# input2.net
KiCad netlist of a schematic drawn in Altium Designer
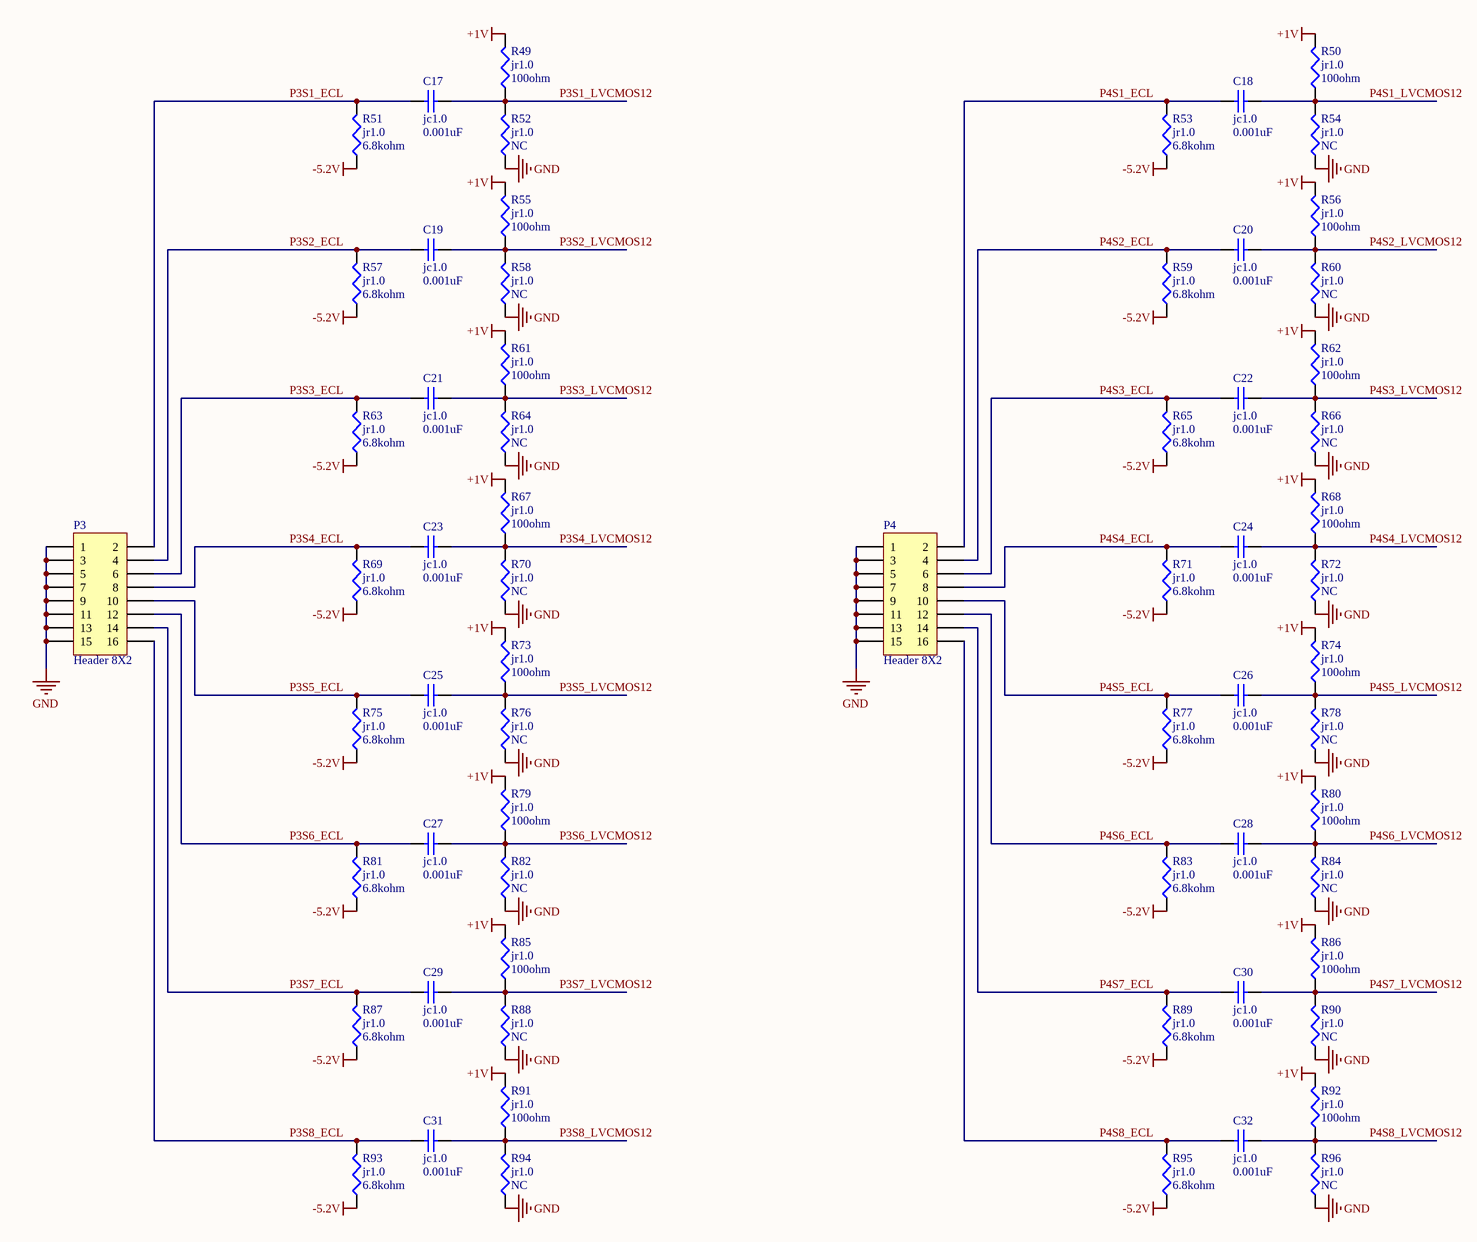
[diagram p0: input2.SchDoc]

(export (version "E")
  (design (tool "Eeschema 10.0.6"))
  (components
    (comp (ref "C17")
      (value "jc1.0")
      (footprint "0402")
      (description "Capacitor")
      (fields (field (name "ALTIUM_VALUE") "0.001uF") (field (name "PUBLISHER") "Altium Limited"))
      (libsource (lib "LIB01DXP2006SchLib") (part "Cap"))
    )
    (comp (ref "C18")
      (value "jc1.0")
      (footprint "0402")
      (description "Capacitor")
      (fields (field (name "ALTIUM_VALUE") "0.001uF") (field (name "PUBLISHER") "Altium Limited"))
      (libsource (lib "LIB01DXP2006SchLib") (part "Cap"))
    )
    (comp (ref "C19")
      (value "jc1.0")
      (footprint "0402")
      (description "Capacitor")
      (fields (field (name "ALTIUM_VALUE") "0.001uF") (field (name "PUBLISHER") "Altium Limited"))
      (libsource (lib "LIB01DXP2006SchLib") (part "Cap"))
    )
    (comp (ref "C20")
      (value "jc1.0")
      (footprint "0402")
      (description "Capacitor")
      (fields (field (name "ALTIUM_VALUE") "0.001uF") (field (name "PUBLISHER") "Altium Limited"))
      (libsource (lib "LIB01DXP2006SchLib") (part "Cap"))
    )
    (comp (ref "C21")
      (value "jc1.0")
      (footprint "0402")
      (description "Capacitor")
      (fields (field (name "ALTIUM_VALUE") "0.001uF") (field (name "PUBLISHER") "Altium Limited"))
      (libsource (lib "LIB01DXP2006SchLib") (part "Cap"))
    )
    (comp (ref "C22")
      (value "jc1.0")
      (footprint "0402")
      (description "Capacitor")
      (fields (field (name "ALTIUM_VALUE") "0.001uF") (field (name "PUBLISHER") "Altium Limited"))
      (libsource (lib "LIB01DXP2006SchLib") (part "Cap"))
    )
    (comp (ref "C23")
      (value "jc1.0")
      (footprint "0402")
      (description "Capacitor")
      (fields (field (name "ALTIUM_VALUE") "0.001uF") (field (name "PUBLISHER") "Altium Limited"))
      (libsource (lib "LIB01DXP2006SchLib") (part "Cap"))
    )
    (comp (ref "C24")
      (value "jc1.0")
      (footprint "0402")
      (description "Capacitor")
      (fields (field (name "ALTIUM_VALUE") "0.001uF") (field (name "PUBLISHER") "Altium Limited"))
      (libsource (lib "LIB01DXP2006SchLib") (part "Cap"))
    )
    (comp (ref "C25")
      (value "jc1.0")
      (footprint "0402")
      (description "Capacitor")
      (fields (field (name "ALTIUM_VALUE") "0.001uF") (field (name "PUBLISHER") "Altium Limited"))
      (libsource (lib "LIB01DXP2006SchLib") (part "Cap"))
    )
    (comp (ref "C26")
      (value "jc1.0")
      (footprint "0402")
      (description "Capacitor")
      (fields (field (name "ALTIUM_VALUE") "0.001uF") (field (name "PUBLISHER") "Altium Limited"))
      (libsource (lib "LIB01DXP2006SchLib") (part "Cap"))
    )
    (comp (ref "C27")
      (value "jc1.0")
      (footprint "0402")
      (description "Capacitor")
      (fields (field (name "ALTIUM_VALUE") "0.001uF") (field (name "PUBLISHER") "Altium Limited"))
      (libsource (lib "LIB01DXP2006SchLib") (part "Cap"))
    )
    (comp (ref "C28")
      (value "jc1.0")
      (footprint "0402")
      (description "Capacitor")
      (fields (field (name "ALTIUM_VALUE") "0.001uF") (field (name "PUBLISHER") "Altium Limited"))
      (libsource (lib "LIB01DXP2006SchLib") (part "Cap"))
    )
    (comp (ref "C29")
      (value "jc1.0")
      (footprint "0402")
      (description "Capacitor")
      (fields (field (name "ALTIUM_VALUE") "0.001uF") (field (name "PUBLISHER") "Altium Limited"))
      (libsource (lib "LIB01DXP2006SchLib") (part "Cap"))
    )
    (comp (ref "C30")
      (value "jc1.0")
      (footprint "0402")
      (description "Capacitor")
      (fields (field (name "ALTIUM_VALUE") "0.001uF") (field (name "PUBLISHER") "Altium Limited"))
      (libsource (lib "LIB01DXP2006SchLib") (part "Cap"))
    )
    (comp (ref "C31")
      (value "jc1.0")
      (footprint "0402")
      (description "Capacitor")
      (fields (field (name "ALTIUM_VALUE") "0.001uF") (field (name "PUBLISHER") "Altium Limited"))
      (libsource (lib "LIB01DXP2006SchLib") (part "Cap"))
    )
    (comp (ref "C32")
      (value "jc1.0")
      (footprint "0402")
      (description "Capacitor")
      (fields (field (name "ALTIUM_VALUE") "0.001uF") (field (name "PUBLISHER") "Altium Limited"))
      (libsource (lib "LIB01DXP2006SchLib") (part "Cap"))
    )
    (comp (ref "P3")
      (value "Header 8X2")
      (footprint "HDR2X8")
      (description "Header, 8-Pin, Dual row")
      (fields (field (name "PUBLISHER") "Altium Limited"))
      (libsource (lib "Miscellaneous Connectors") (part "Header 8X2"))
    )
    (comp (ref "P4")
      (value "Header 8X2")
      (footprint "HDR2X8")
      (description "Header, 8-Pin, Dual row")
      (fields (field (name "PUBLISHER") "Altium Limited"))
      (libsource (lib "Miscellaneous Connectors") (part "Header 8X2"))
    )
    (comp (ref "R49")
      (value "jr1.0")
      (footprint "0402")
      (description "Resistor")
      (fields (field (name "ALTIUM_VALUE") "100ohm") (field (name "PUBLISHER") "Altium Limited"))
      (libsource (lib "LIB01DXP2006SchLib") (part "Res"))
    )
    (comp (ref "R50")
      (value "jr1.0")
      (footprint "0402")
      (description "Resistor")
      (fields (field (name "ALTIUM_VALUE") "100ohm") (field (name "PUBLISHER") "Altium Limited"))
      (libsource (lib "LIB01DXP2006SchLib") (part "Res"))
    )
    (comp (ref "R51")
      (value "jr1.0")
      (footprint "0402")
      (description "Resistor")
      (fields (field (name "ALTIUM_VALUE") "6.8kohm") (field (name "PUBLISHER") "Altium Limited"))
      (libsource (lib "LIB01DXP2006SchLib") (part "Res"))
    )
    (comp (ref "R52")
      (value "jr1.0")
      (footprint "0402")
      (description "Resistor")
      (fields (field (name "ALTIUM_VALUE") "NC") (field (name "PUBLISHER") "Altium Limited"))
      (libsource (lib "LIB01DXP2006SchLib") (part "Res"))
    )
    (comp (ref "R53")
      (value "jr1.0")
      (footprint "0402")
      (description "Resistor")
      (fields (field (name "ALTIUM_VALUE") "6.8kohm") (field (name "PUBLISHER") "Altium Limited"))
      (libsource (lib "LIB01DXP2006SchLib") (part "Res"))
    )
    (comp (ref "R54")
      (value "jr1.0")
      (footprint "0402")
      (description "Resistor")
      (fields (field (name "ALTIUM_VALUE") "NC") (field (name "PUBLISHER") "Altium Limited"))
      (libsource (lib "LIB01DXP2006SchLib") (part "Res"))
    )
    (comp (ref "R55")
      (value "jr1.0")
      (footprint "0402")
      (description "Resistor")
      (fields (field (name "ALTIUM_VALUE") "100ohm") (field (name "PUBLISHER") "Altium Limited"))
      (libsource (lib "LIB01DXP2006SchLib") (part "Res"))
    )
    (comp (ref "R56")
      (value "jr1.0")
      (footprint "0402")
      (description "Resistor")
      (fields (field (name "ALTIUM_VALUE") "100ohm") (field (name "PUBLISHER") "Altium Limited"))
      (libsource (lib "LIB01DXP2006SchLib") (part "Res"))
    )
    (comp (ref "R57")
      (value "jr1.0")
      (footprint "0402")
      (description "Resistor")
      (fields (field (name "ALTIUM_VALUE") "6.8kohm") (field (name "PUBLISHER") "Altium Limited"))
      (libsource (lib "LIB01DXP2006SchLib") (part "Res"))
    )
    (comp (ref "R58")
      (value "jr1.0")
      (footprint "0402")
      (description "Resistor")
      (fields (field (name "ALTIUM_VALUE") "NC") (field (name "PUBLISHER") "Altium Limited"))
      (libsource (lib "LIB01DXP2006SchLib") (part "Res"))
    )
    (comp (ref "R59")
      (value "jr1.0")
      (footprint "0402")
      (description "Resistor")
      (fields (field (name "ALTIUM_VALUE") "6.8kohm") (field (name "PUBLISHER") "Altium Limited"))
      (libsource (lib "LIB01DXP2006SchLib") (part "Res"))
    )
    (comp (ref "R60")
      (value "jr1.0")
      (footprint "0402")
      (description "Resistor")
      (fields (field (name "ALTIUM_VALUE") "NC") (field (name "PUBLISHER") "Altium Limited"))
      (libsource (lib "LIB01DXP2006SchLib") (part "Res"))
    )
    (comp (ref "R61")
      (value "jr1.0")
      (footprint "0402")
      (description "Resistor")
      (fields (field (name "ALTIUM_VALUE") "100ohm") (field (name "PUBLISHER") "Altium Limited"))
      (libsource (lib "LIB01DXP2006SchLib") (part "Res"))
    )
    (comp (ref "R62")
      (value "jr1.0")
      (footprint "0402")
      (description "Resistor")
      (fields (field (name "ALTIUM_VALUE") "100ohm") (field (name "PUBLISHER") "Altium Limited"))
      (libsource (lib "LIB01DXP2006SchLib") (part "Res"))
    )
    (comp (ref "R63")
      (value "jr1.0")
      (footprint "0402")
      (description "Resistor")
      (fields (field (name "ALTIUM_VALUE") "6.8kohm") (field (name "PUBLISHER") "Altium Limited"))
      (libsource (lib "LIB01DXP2006SchLib") (part "Res"))
    )
    (comp (ref "R64")
      (value "jr1.0")
      (footprint "0402")
      (description "Resistor")
      (fields (field (name "ALTIUM_VALUE") "NC") (field (name "PUBLISHER") "Altium Limited"))
      (libsource (lib "LIB01DXP2006SchLib") (part "Res"))
    )
    (comp (ref "R65")
      (value "jr1.0")
      (footprint "0402")
      (description "Resistor")
      (fields (field (name "ALTIUM_VALUE") "6.8kohm") (field (name "PUBLISHER") "Altium Limited"))
      (libsource (lib "LIB01DXP2006SchLib") (part "Res"))
    )
    (comp (ref "R66")
      (value "jr1.0")
      (footprint "0402")
      (description "Resistor")
      (fields (field (name "ALTIUM_VALUE") "NC") (field (name "PUBLISHER") "Altium Limited"))
      (libsource (lib "LIB01DXP2006SchLib") (part "Res"))
    )
    (comp (ref "R67")
      (value "jr1.0")
      (footprint "0402")
      (description "Resistor")
      (fields (field (name "ALTIUM_VALUE") "100ohm") (field (name "PUBLISHER") "Altium Limited"))
      (libsource (lib "LIB01DXP2006SchLib") (part "Res"))
    )
    (comp (ref "R68")
      (value "jr1.0")
      (footprint "0402")
      (description "Resistor")
      (fields (field (name "ALTIUM_VALUE") "100ohm") (field (name "PUBLISHER") "Altium Limited"))
      (libsource (lib "LIB01DXP2006SchLib") (part "Res"))
    )
    (comp (ref "R69")
      (value "jr1.0")
      (footprint "0402")
      (description "Resistor")
      (fields (field (name "ALTIUM_VALUE") "6.8kohm") (field (name "PUBLISHER") "Altium Limited"))
      (libsource (lib "LIB01DXP2006SchLib") (part "Res"))
    )
    (comp (ref "R70")
      (value "jr1.0")
      (footprint "0402")
      (description "Resistor")
      (fields (field (name "ALTIUM_VALUE") "NC") (field (name "PUBLISHER") "Altium Limited"))
      (libsource (lib "LIB01DXP2006SchLib") (part "Res"))
    )
    (comp (ref "R71")
      (value "jr1.0")
      (footprint "0402")
      (description "Resistor")
      (fields (field (name "ALTIUM_VALUE") "6.8kohm") (field (name "PUBLISHER") "Altium Limited"))
      (libsource (lib "LIB01DXP2006SchLib") (part "Res"))
    )
    (comp (ref "R72")
      (value "jr1.0")
      (footprint "0402")
      (description "Resistor")
      (fields (field (name "ALTIUM_VALUE") "NC") (field (name "PUBLISHER") "Altium Limited"))
      (libsource (lib "LIB01DXP2006SchLib") (part "Res"))
    )
    (comp (ref "R73")
      (value "jr1.0")
      (footprint "0402")
      (description "Resistor")
      (fields (field (name "ALTIUM_VALUE") "100ohm") (field (name "PUBLISHER") "Altium Limited"))
      (libsource (lib "LIB01DXP2006SchLib") (part "Res"))
    )
    (comp (ref "R74")
      (value "jr1.0")
      (footprint "0402")
      (description "Resistor")
      (fields (field (name "ALTIUM_VALUE") "100ohm") (field (name "PUBLISHER") "Altium Limited"))
      (libsource (lib "LIB01DXP2006SchLib") (part "Res"))
    )
    (comp (ref "R75")
      (value "jr1.0")
      (footprint "0402")
      (description "Resistor")
      (fields (field (name "ALTIUM_VALUE") "6.8kohm") (field (name "PUBLISHER") "Altium Limited"))
      (libsource (lib "LIB01DXP2006SchLib") (part "Res"))
    )
    (comp (ref "R76")
      (value "jr1.0")
      (footprint "0402")
      (description "Resistor")
      (fields (field (name "ALTIUM_VALUE") "NC") (field (name "PUBLISHER") "Altium Limited"))
      (libsource (lib "LIB01DXP2006SchLib") (part "Res"))
    )
    (comp (ref "R77")
      (value "jr1.0")
      (footprint "0402")
      (description "Resistor")
      (fields (field (name "ALTIUM_VALUE") "6.8kohm") (field (name "PUBLISHER") "Altium Limited"))
      (libsource (lib "LIB01DXP2006SchLib") (part "Res"))
    )
    (comp (ref "R78")
      (value "jr1.0")
      (footprint "0402")
      (description "Resistor")
      (fields (field (name "ALTIUM_VALUE") "NC") (field (name "PUBLISHER") "Altium Limited"))
      (libsource (lib "LIB01DXP2006SchLib") (part "Res"))
    )
    (comp (ref "R79")
      (value "jr1.0")
      (footprint "0402")
      (description "Resistor")
      (fields (field (name "ALTIUM_VALUE") "100ohm") (field (name "PUBLISHER") "Altium Limited"))
      (libsource (lib "LIB01DXP2006SchLib") (part "Res"))
    )
    (comp (ref "R80")
      (value "jr1.0")
      (footprint "0402")
      (description "Resistor")
      (fields (field (name "ALTIUM_VALUE") "100ohm") (field (name "PUBLISHER") "Altium Limited"))
      (libsource (lib "LIB01DXP2006SchLib") (part "Res"))
    )
    (comp (ref "R81")
      (value "jr1.0")
      (footprint "0402")
      (description "Resistor")
      (fields (field (name "ALTIUM_VALUE") "6.8kohm") (field (name "PUBLISHER") "Altium Limited"))
      (libsource (lib "LIB01DXP2006SchLib") (part "Res"))
    )
    (comp (ref "R82")
      (value "jr1.0")
      (footprint "0402")
      (description "Resistor")
      (fields (field (name "ALTIUM_VALUE") "NC") (field (name "PUBLISHER") "Altium Limited"))
      (libsource (lib "LIB01DXP2006SchLib") (part "Res"))
    )
    (comp (ref "R83")
      (value "jr1.0")
      (footprint "0402")
      (description "Resistor")
      (fields (field (name "ALTIUM_VALUE") "6.8kohm") (field (name "PUBLISHER") "Altium Limited"))
      (libsource (lib "LIB01DXP2006SchLib") (part "Res"))
    )
    (comp (ref "R84")
      (value "jr1.0")
      (footprint "0402")
      (description "Resistor")
      (fields (field (name "ALTIUM_VALUE") "NC") (field (name "PUBLISHER") "Altium Limited"))
      (libsource (lib "LIB01DXP2006SchLib") (part "Res"))
    )
    (comp (ref "R85")
      (value "jr1.0")
      (footprint "0402")
      (description "Resistor")
      (fields (field (name "ALTIUM_VALUE") "100ohm") (field (name "PUBLISHER") "Altium Limited"))
      (libsource (lib "LIB01DXP2006SchLib") (part "Res"))
    )
    (comp (ref "R86")
      (value "jr1.0")
      (footprint "0402")
      (description "Resistor")
      (fields (field (name "ALTIUM_VALUE") "100ohm") (field (name "PUBLISHER") "Altium Limited"))
      (libsource (lib "LIB01DXP2006SchLib") (part "Res"))
    )
    (comp (ref "R87")
      (value "jr1.0")
      (footprint "0402")
      (description "Resistor")
      (fields (field (name "ALTIUM_VALUE") "6.8kohm") (field (name "PUBLISHER") "Altium Limited"))
      (libsource (lib "LIB01DXP2006SchLib") (part "Res"))
    )
    (comp (ref "R88")
      (value "jr1.0")
      (footprint "0402")
      (description "Resistor")
      (fields (field (name "ALTIUM_VALUE") "NC") (field (name "PUBLISHER") "Altium Limited"))
      (libsource (lib "LIB01DXP2006SchLib") (part "Res"))
    )
    (comp (ref "R89")
      (value "jr1.0")
      (footprint "0402")
      (description "Resistor")
      (fields (field (name "ALTIUM_VALUE") "6.8kohm") (field (name "PUBLISHER") "Altium Limited"))
      (libsource (lib "LIB01DXP2006SchLib") (part "Res"))
    )
    (comp (ref "R90")
      (value "jr1.0")
      (footprint "0402")
      (description "Resistor")
      (fields (field (name "ALTIUM_VALUE") "NC") (field (name "PUBLISHER") "Altium Limited"))
      (libsource (lib "LIB01DXP2006SchLib") (part "Res"))
    )
    (comp (ref "R91")
      (value "jr1.0")
      (footprint "0402")
      (description "Resistor")
      (fields (field (name "ALTIUM_VALUE") "100ohm") (field (name "PUBLISHER") "Altium Limited"))
      (libsource (lib "LIB01DXP2006SchLib") (part "Res"))
    )
    (comp (ref "R92")
      (value "jr1.0")
      (footprint "0402")
      (description "Resistor")
      (fields (field (name "ALTIUM_VALUE") "100ohm") (field (name "PUBLISHER") "Altium Limited"))
      (libsource (lib "LIB01DXP2006SchLib") (part "Res"))
    )
    (comp (ref "R93")
      (value "jr1.0")
      (footprint "0402")
      (description "Resistor")
      (fields (field (name "ALTIUM_VALUE") "6.8kohm") (field (name "PUBLISHER") "Altium Limited"))
      (libsource (lib "LIB01DXP2006SchLib") (part "Res"))
    )
    (comp (ref "R94")
      (value "jr1.0")
      (footprint "0402")
      (description "Resistor")
      (fields (field (name "ALTIUM_VALUE") "NC") (field (name "PUBLISHER") "Altium Limited"))
      (libsource (lib "LIB01DXP2006SchLib") (part "Res"))
    )
    (comp (ref "R95")
      (value "jr1.0")
      (footprint "0402")
      (description "Resistor")
      (fields (field (name "ALTIUM_VALUE") "6.8kohm") (field (name "PUBLISHER") "Altium Limited"))
      (libsource (lib "LIB01DXP2006SchLib") (part "Res"))
    )
    (comp (ref "R96")
      (value "jr1.0")
      (footprint "0402")
      (description "Resistor")
      (fields (field (name "ALTIUM_VALUE") "NC") (field (name "PUBLISHER") "Altium Limited"))
      (libsource (lib "LIB01DXP2006SchLib") (part "Res"))
    )
  )
  (nets
    (net (code "1") (name "+1V") (class "Default")
      (node (ref "R49") (pin "2") (pinfunction "2_2") (pintype "passive"))
      (node (ref "R50") (pin "2") (pinfunction "2_2") (pintype "passive"))
      (node (ref "R55") (pin "2") (pinfunction "2_2") (pintype "passive"))
      (node (ref "R56") (pin "2") (pinfunction "2_2") (pintype "passive"))
      (node (ref "R61") (pin "2") (pinfunction "2_2") (pintype "passive"))
      (node (ref "R62") (pin "2") (pinfunction "2_2") (pintype "passive"))
      (node (ref "R67") (pin "2") (pinfunction "2_2") (pintype "passive"))
      (node (ref "R68") (pin "2") (pinfunction "2_2") (pintype "passive"))
      (node (ref "R73") (pin "2") (pinfunction "2_2") (pintype "passive"))
      (node (ref "R74") (pin "2") (pinfunction "2_2") (pintype "passive"))
      (node (ref "R79") (pin "2") (pinfunction "2_2") (pintype "passive"))
      (node (ref "R80") (pin "2") (pinfunction "2_2") (pintype "passive"))
      (node (ref "R85") (pin "2") (pinfunction "2_2") (pintype "passive"))
      (node (ref "R86") (pin "2") (pinfunction "2_2") (pintype "passive"))
      (node (ref "R91") (pin "2") (pinfunction "2_2") (pintype "passive"))
      (node (ref "R92") (pin "2") (pinfunction "2_2") (pintype "passive"))
    )
    (net (code "2") (name "-5.2V") (class "Default")
      (node (ref "R51") (pin "1") (pinfunction "1_1") (pintype "passive"))
      (node (ref "R53") (pin "1") (pinfunction "1_1") (pintype "passive"))
      (node (ref "R57") (pin "1") (pinfunction "1_1") (pintype "passive"))
      (node (ref "R59") (pin "1") (pinfunction "1_1") (pintype "passive"))
      (node (ref "R63") (pin "1") (pinfunction "1_1") (pintype "passive"))
      (node (ref "R65") (pin "1") (pinfunction "1_1") (pintype "passive"))
      (node (ref "R69") (pin "1") (pinfunction "1_1") (pintype "passive"))
      (node (ref "R71") (pin "1") (pinfunction "1_1") (pintype "passive"))
      (node (ref "R75") (pin "1") (pinfunction "1_1") (pintype "passive"))
      (node (ref "R77") (pin "1") (pinfunction "1_1") (pintype "passive"))
      (node (ref "R81") (pin "1") (pinfunction "1_1") (pintype "passive"))
      (node (ref "R83") (pin "1") (pinfunction "1_1") (pintype "passive"))
      (node (ref "R87") (pin "1") (pinfunction "1_1") (pintype "passive"))
      (node (ref "R89") (pin "1") (pinfunction "1_1") (pintype "passive"))
      (node (ref "R93") (pin "1") (pinfunction "1_1") (pintype "passive"))
      (node (ref "R95") (pin "1") (pinfunction "1_1") (pintype "passive"))
    )
    (net (code "3") (name "/P3S1_ECL") (class "Default")
      (node (ref "C17") (pin "1") (pinfunction "1_1") (pintype "passive"))
      (node (ref "P3") (pin "2") (pinfunction "2_2") (pintype "passive"))
      (node (ref "R51") (pin "2") (pinfunction "2_2") (pintype "passive"))
    )
    (net (code "4") (name "/P3S1_LVCMOS12") (class "Default")
      (node (ref "C17") (pin "2") (pinfunction "2_2") (pintype "passive"))
      (node (ref "R49") (pin "1") (pinfunction "1_1") (pintype "passive"))
      (node (ref "R52") (pin "2") (pinfunction "2_2") (pintype "passive"))
    )
    (net (code "5") (name "/P3S2_ECL") (class "Default")
      (node (ref "C19") (pin "1") (pinfunction "1_1") (pintype "passive"))
      (node (ref "P3") (pin "4") (pinfunction "4_4") (pintype "passive"))
      (node (ref "R57") (pin "2") (pinfunction "2_2") (pintype "passive"))
    )
    (net (code "6") (name "/P3S2_LVCMOS12") (class "Default")
      (node (ref "C19") (pin "2") (pinfunction "2_2") (pintype "passive"))
      (node (ref "R55") (pin "1") (pinfunction "1_1") (pintype "passive"))
      (node (ref "R58") (pin "2") (pinfunction "2_2") (pintype "passive"))
    )
    (net (code "7") (name "/P3S3_ECL") (class "Default")
      (node (ref "C21") (pin "1") (pinfunction "1_1") (pintype "passive"))
      (node (ref "P3") (pin "6") (pinfunction "6_6") (pintype "passive"))
      (node (ref "R63") (pin "2") (pinfunction "2_2") (pintype "passive"))
    )
    (net (code "8") (name "/P3S3_LVCMOS12") (class "Default")
      (node (ref "C21") (pin "2") (pinfunction "2_2") (pintype "passive"))
      (node (ref "R61") (pin "1") (pinfunction "1_1") (pintype "passive"))
      (node (ref "R64") (pin "2") (pinfunction "2_2") (pintype "passive"))
    )
    (net (code "9") (name "/P3S4_ECL") (class "Default")
      (node (ref "C23") (pin "1") (pinfunction "1_1") (pintype "passive"))
      (node (ref "P3") (pin "8") (pinfunction "8_8") (pintype "passive"))
      (node (ref "R69") (pin "2") (pinfunction "2_2") (pintype "passive"))
    )
    (net (code "10") (name "/P3S4_LVCMOS12") (class "Default")
      (node (ref "C23") (pin "2") (pinfunction "2_2") (pintype "passive"))
      (node (ref "R67") (pin "1") (pinfunction "1_1") (pintype "passive"))
      (node (ref "R70") (pin "2") (pinfunction "2_2") (pintype "passive"))
    )
    (net (code "11") (name "/P3S5_ECL") (class "Default")
      (node (ref "C25") (pin "1") (pinfunction "1_1") (pintype "passive"))
      (node (ref "P3") (pin "10") (pinfunction "10_10") (pintype "passive"))
      (node (ref "R75") (pin "2") (pinfunction "2_2") (pintype "passive"))
    )
    (net (code "12") (name "/P3S5_LVCMOS12") (class "Default")
      (node (ref "C25") (pin "2") (pinfunction "2_2") (pintype "passive"))
      (node (ref "R73") (pin "1") (pinfunction "1_1") (pintype "passive"))
      (node (ref "R76") (pin "2") (pinfunction "2_2") (pintype "passive"))
    )
    (net (code "13") (name "/P3S6_ECL") (class "Default")
      (node (ref "C27") (pin "1") (pinfunction "1_1") (pintype "passive"))
      (node (ref "P3") (pin "12") (pinfunction "12_12") (pintype "passive"))
      (node (ref "R81") (pin "2") (pinfunction "2_2") (pintype "passive"))
    )
    (net (code "14") (name "/P3S6_LVCMOS12") (class "Default")
      (node (ref "C27") (pin "2") (pinfunction "2_2") (pintype "passive"))
      (node (ref "R79") (pin "1") (pinfunction "1_1") (pintype "passive"))
      (node (ref "R82") (pin "2") (pinfunction "2_2") (pintype "passive"))
    )
    (net (code "15") (name "/P3S7_ECL") (class "Default")
      (node (ref "C29") (pin "1") (pinfunction "1_1") (pintype "passive"))
      (node (ref "P3") (pin "14") (pinfunction "14_14") (pintype "passive"))
      (node (ref "R87") (pin "2") (pinfunction "2_2") (pintype "passive"))
    )
    (net (code "16") (name "/P3S7_LVCMOS12") (class "Default")
      (node (ref "C29") (pin "2") (pinfunction "2_2") (pintype "passive"))
      (node (ref "R85") (pin "1") (pinfunction "1_1") (pintype "passive"))
      (node (ref "R88") (pin "2") (pinfunction "2_2") (pintype "passive"))
    )
    (net (code "17") (name "/P3S8_ECL") (class "Default")
      (node (ref "C31") (pin "1") (pinfunction "1_1") (pintype "passive"))
      (node (ref "P3") (pin "16") (pinfunction "16_16") (pintype "passive"))
      (node (ref "R93") (pin "2") (pinfunction "2_2") (pintype "passive"))
    )
    (net (code "18") (name "/P3S8_LVCMOS12") (class "Default")
      (node (ref "C31") (pin "2") (pinfunction "2_2") (pintype "passive"))
      (node (ref "R91") (pin "1") (pinfunction "1_1") (pintype "passive"))
      (node (ref "R94") (pin "2") (pinfunction "2_2") (pintype "passive"))
    )
    (net (code "19") (name "/P4S1_ECL") (class "Default")
      (node (ref "C18") (pin "1") (pinfunction "1_1") (pintype "passive"))
      (node (ref "P4") (pin "2") (pinfunction "2_2") (pintype "passive"))
      (node (ref "R53") (pin "2") (pinfunction "2_2") (pintype "passive"))
    )
    (net (code "20") (name "/P4S1_LVCMOS12") (class "Default")
      (node (ref "C18") (pin "2") (pinfunction "2_2") (pintype "passive"))
      (node (ref "R50") (pin "1") (pinfunction "1_1") (pintype "passive"))
      (node (ref "R54") (pin "2") (pinfunction "2_2") (pintype "passive"))
    )
    (net (code "21") (name "/P4S2_ECL") (class "Default")
      (node (ref "C20") (pin "1") (pinfunction "1_1") (pintype "passive"))
      (node (ref "P4") (pin "4") (pinfunction "4_4") (pintype "passive"))
      (node (ref "R59") (pin "2") (pinfunction "2_2") (pintype "passive"))
    )
    (net (code "22") (name "/P4S2_LVCMOS12") (class "Default")
      (node (ref "C20") (pin "2") (pinfunction "2_2") (pintype "passive"))
      (node (ref "R56") (pin "1") (pinfunction "1_1") (pintype "passive"))
      (node (ref "R60") (pin "2") (pinfunction "2_2") (pintype "passive"))
    )
    (net (code "23") (name "/P4S3_ECL") (class "Default")
      (node (ref "C22") (pin "1") (pinfunction "1_1") (pintype "passive"))
      (node (ref "P4") (pin "6") (pinfunction "6_6") (pintype "passive"))
      (node (ref "R65") (pin "2") (pinfunction "2_2") (pintype "passive"))
    )
    (net (code "24") (name "/P4S3_LVCMOS12") (class "Default")
      (node (ref "C22") (pin "2") (pinfunction "2_2") (pintype "passive"))
      (node (ref "R62") (pin "1") (pinfunction "1_1") (pintype "passive"))
      (node (ref "R66") (pin "2") (pinfunction "2_2") (pintype "passive"))
    )
    (net (code "25") (name "/P4S4_ECL") (class "Default")
      (node (ref "C24") (pin "1") (pinfunction "1_1") (pintype "passive"))
      (node (ref "P4") (pin "8") (pinfunction "8_8") (pintype "passive"))
      (node (ref "R71") (pin "2") (pinfunction "2_2") (pintype "passive"))
    )
    (net (code "26") (name "/P4S4_LVCMOS12") (class "Default")
      (node (ref "C24") (pin "2") (pinfunction "2_2") (pintype "passive"))
      (node (ref "R68") (pin "1") (pinfunction "1_1") (pintype "passive"))
      (node (ref "R72") (pin "2") (pinfunction "2_2") (pintype "passive"))
    )
    (net (code "27") (name "/P4S5_ECL") (class "Default")
      (node (ref "C26") (pin "1") (pinfunction "1_1") (pintype "passive"))
      (node (ref "P4") (pin "10") (pinfunction "10_10") (pintype "passive"))
      (node (ref "R77") (pin "2") (pinfunction "2_2") (pintype "passive"))
    )
    (net (code "28") (name "/P4S5_LVCMOS12") (class "Default")
      (node (ref "C26") (pin "2") (pinfunction "2_2") (pintype "passive"))
      (node (ref "R74") (pin "1") (pinfunction "1_1") (pintype "passive"))
      (node (ref "R78") (pin "2") (pinfunction "2_2") (pintype "passive"))
    )
    (net (code "29") (name "/P4S6_ECL") (class "Default")
      (node (ref "C28") (pin "1") (pinfunction "1_1") (pintype "passive"))
      (node (ref "P4") (pin "12") (pinfunction "12_12") (pintype "passive"))
      (node (ref "R83") (pin "2") (pinfunction "2_2") (pintype "passive"))
    )
    (net (code "30") (name "/P4S6_LVCMOS12") (class "Default")
      (node (ref "C28") (pin "2") (pinfunction "2_2") (pintype "passive"))
      (node (ref "R80") (pin "1") (pinfunction "1_1") (pintype "passive"))
      (node (ref "R84") (pin "2") (pinfunction "2_2") (pintype "passive"))
    )
    (net (code "31") (name "/P4S7_ECL") (class "Default")
      (node (ref "C30") (pin "1") (pinfunction "1_1") (pintype "passive"))
      (node (ref "P4") (pin "14") (pinfunction "14_14") (pintype "passive"))
      (node (ref "R89") (pin "2") (pinfunction "2_2") (pintype "passive"))
    )
    (net (code "32") (name "/P4S7_LVCMOS12") (class "Default")
      (node (ref "C30") (pin "2") (pinfunction "2_2") (pintype "passive"))
      (node (ref "R86") (pin "1") (pinfunction "1_1") (pintype "passive"))
      (node (ref "R90") (pin "2") (pinfunction "2_2") (pintype "passive"))
    )
    (net (code "33") (name "/P4S8_ECL") (class "Default")
      (node (ref "C32") (pin "1") (pinfunction "1_1") (pintype "passive"))
      (node (ref "P4") (pin "16") (pinfunction "16_16") (pintype "passive"))
      (node (ref "R95") (pin "2") (pinfunction "2_2") (pintype "passive"))
    )
    (net (code "34") (name "/P4S8_LVCMOS12") (class "Default")
      (node (ref "C32") (pin "2") (pinfunction "2_2") (pintype "passive"))
      (node (ref "R92") (pin "1") (pinfunction "1_1") (pintype "passive"))
      (node (ref "R96") (pin "2") (pinfunction "2_2") (pintype "passive"))
    )
    (net (code "35") (name "GND") (class "Default")
      (node (ref "P3") (pin "1") (pinfunction "1_1") (pintype "passive"))
      (node (ref "P3") (pin "11") (pinfunction "11_11") (pintype "passive"))
      (node (ref "P3") (pin "13") (pinfunction "13_13") (pintype "passive"))
      (node (ref "P3") (pin "15") (pinfunction "15_15") (pintype "passive"))
      (node (ref "P3") (pin "3") (pinfunction "3_3") (pintype "passive"))
      (node (ref "P3") (pin "5") (pinfunction "5_5") (pintype "passive"))
      (node (ref "P3") (pin "7") (pinfunction "7_7") (pintype "passive"))
      (node (ref "P3") (pin "9") (pinfunction "9_9") (pintype "passive"))
      (node (ref "P4") (pin "1") (pinfunction "1_1") (pintype "passive"))
      (node (ref "P4") (pin "11") (pinfunction "11_11") (pintype "passive"))
      (node (ref "P4") (pin "13") (pinfunction "13_13") (pintype "passive"))
      (node (ref "P4") (pin "15") (pinfunction "15_15") (pintype "passive"))
      (node (ref "P4") (pin "3") (pinfunction "3_3") (pintype "passive"))
      (node (ref "P4") (pin "5") (pinfunction "5_5") (pintype "passive"))
      (node (ref "P4") (pin "7") (pinfunction "7_7") (pintype "passive"))
      (node (ref "P4") (pin "9") (pinfunction "9_9") (pintype "passive"))
      (node (ref "R52") (pin "1") (pinfunction "1_1") (pintype "passive"))
      (node (ref "R54") (pin "1") (pinfunction "1_1") (pintype "passive"))
      (node (ref "R58") (pin "1") (pinfunction "1_1") (pintype "passive"))
      (node (ref "R60") (pin "1") (pinfunction "1_1") (pintype "passive"))
      (node (ref "R64") (pin "1") (pinfunction "1_1") (pintype "passive"))
      (node (ref "R66") (pin "1") (pinfunction "1_1") (pintype "passive"))
      (node (ref "R70") (pin "1") (pinfunction "1_1") (pintype "passive"))
      (node (ref "R72") (pin "1") (pinfunction "1_1") (pintype "passive"))
      (node (ref "R76") (pin "1") (pinfunction "1_1") (pintype "passive"))
      (node (ref "R78") (pin "1") (pinfunction "1_1") (pintype "passive"))
      (node (ref "R82") (pin "1") (pinfunction "1_1") (pintype "passive"))
      (node (ref "R84") (pin "1") (pinfunction "1_1") (pintype "passive"))
      (node (ref "R88") (pin "1") (pinfunction "1_1") (pintype "passive"))
      (node (ref "R90") (pin "1") (pinfunction "1_1") (pintype "passive"))
      (node (ref "R94") (pin "1") (pinfunction "1_1") (pintype "passive"))
      (node (ref "R96") (pin "1") (pinfunction "1_1") (pintype "passive"))
    )
  )
)
